# apple_all_pd1.net
KiCad netlist of a schematic drawn in EAGLE
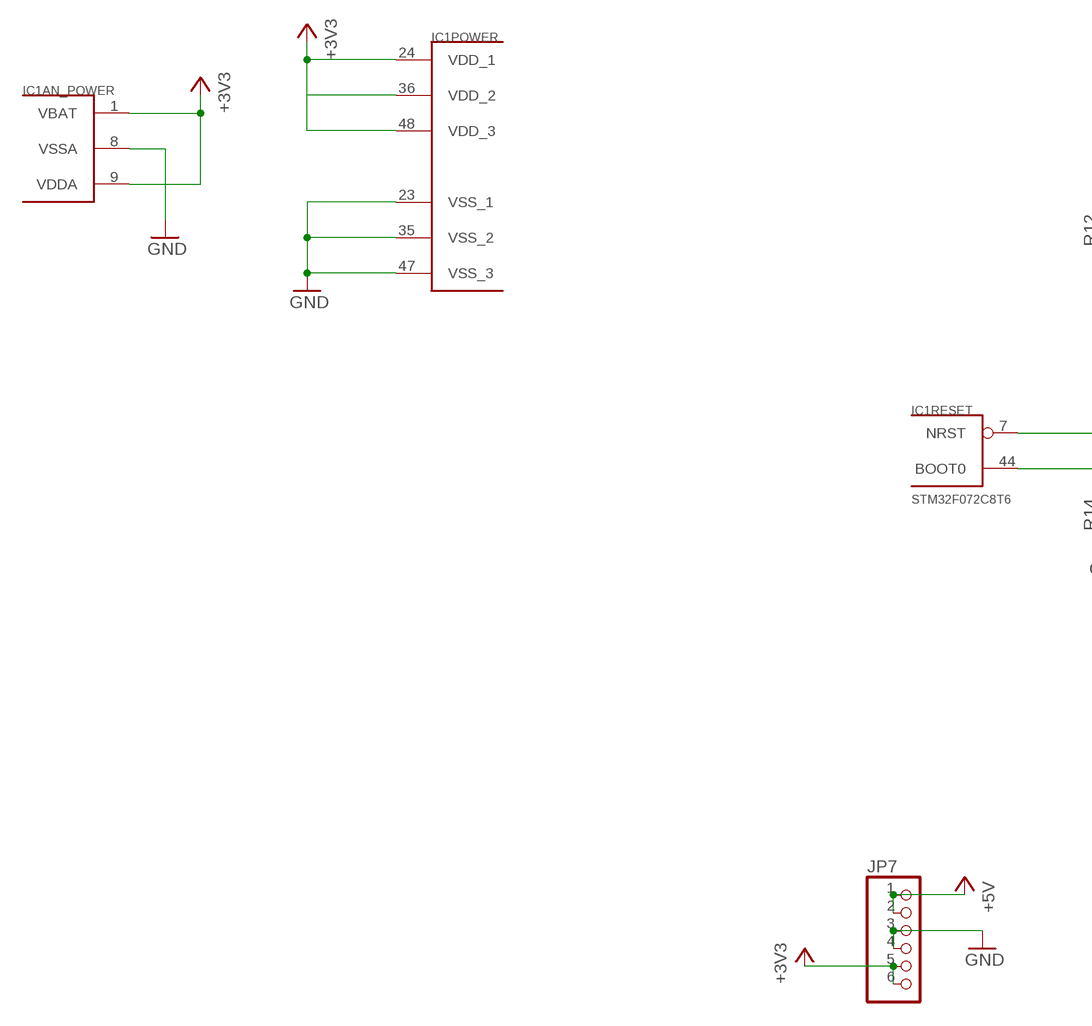
[diagram p0: schematic, sheet 1, part 1 of 2]
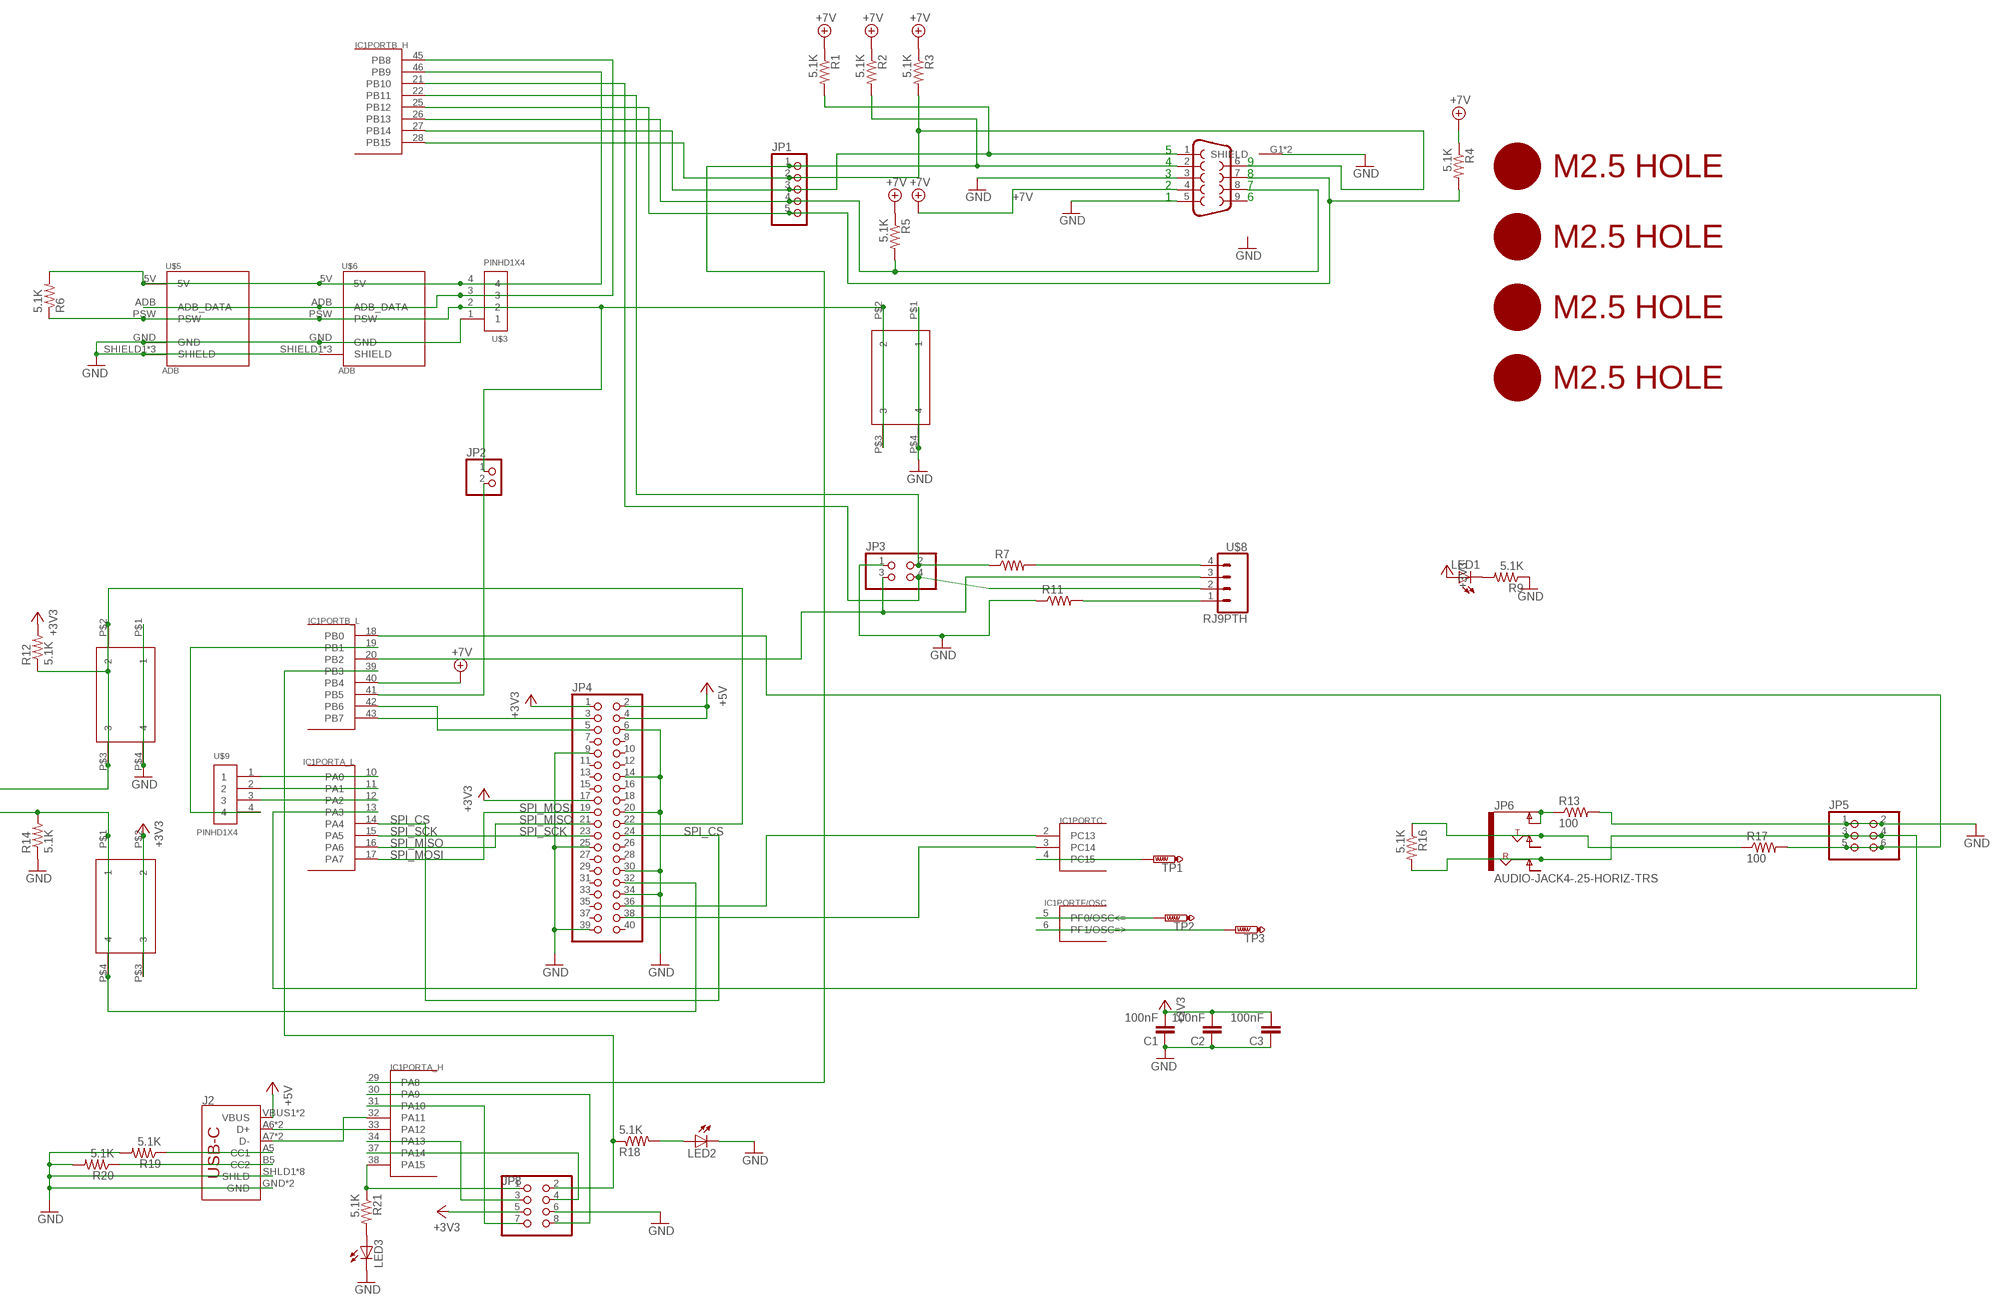
[diagram p1: schematic, sheet 1, part 2 of 2]

(export (version "E")
  (design (tool "Eeschema 10.0.6"))
  (components
    (comp (ref "C1")
      (value "100nF")
      (footprint "eagle-import:0805@1")
      (libsource (lib "eagle-import") (part "CAP0805"))
    )
    (comp (ref "C2")
      (value "100nF")
      (footprint "eagle-import:0805@1")
      (libsource (lib "eagle-import") (part "CAP0805"))
    )
    (comp (ref "C3")
      (value "100nF")
      (footprint "eagle-import:0805@1")
      (libsource (lib "eagle-import") (part "CAP0805"))
    )
    (comp (ref "IC1")
      (value "STM32F072C8T6")
      (footprint "eagle-import:TQFP48")
      (libsource (lib "eagle-import") (part "STM32F072C8T6"))
    )
    (comp (ref "J1")
      (value "DB9FEMALE")
      (footprint "eagle-import:DB9")
      (libsource (lib "eagle-import") (part "DB9FEMALE"))
    )
    (comp (ref "J2")
      (value "USB_C16PIN")
      (footprint "eagle-import:USB-C-16P")
      (libsource (lib "eagle-import") (part "USB_C16PIN"))
    )
    (comp (ref "JP1")
      (value "PINHD-1X5")
      (footprint "eagle-import:1X05")
      (libsource (lib "eagle-import") (part "PINHD-1X5"))
    )
    (comp (ref "JP2")
      (value "PINHD-1X2")
      (footprint "eagle-import:1X02")
      (libsource (lib "eagle-import") (part "PINHD-1X2"))
    )
    (comp (ref "JP3")
      (value "PINHD-2X2")
      (footprint "eagle-import:2X02")
      (libsource (lib "eagle-import") (part "PINHD-2X2"))
    )
    (comp (ref "JP4")
      (value "PINHD-2X20-BIG")
      (footprint "eagle-import:2X20-BIG")
      (libsource (lib "eagle-import") (part "PINHD-2X20-BIG"))
    )
    (comp (ref "JP5")
      (value "PINHD-2X3")
      (footprint "eagle-import:2X03")
      (libsource (lib "eagle-import") (part "PINHD-2X3"))
    )
    (comp (ref "JP6")
      (value "AUDIO-JACK4-.25-HORIZ-TRS")
      (footprint "eagle-import:AUDIO-JACK-.25-INCH-HORIZ-PTH")
      (libsource (lib "eagle-import") (part "AUDIO-JACK4-.25-HORIZ-TRS"))
    )
    (comp (ref "JP7")
      (value "PINHD-1X6CB")
      (footprint "eagle-import:1X06-CLEANBIG")
      (libsource (lib "eagle-import") (part "PINHD-1X6CB"))
    )
    (comp (ref "JP8")
      (value "PINHD-2X4")
      (footprint "eagle-import:2X04")
      (libsource (lib "eagle-import") (part "PINHD-2X4"))
    )
    (comp (ref "LED1")
      (value "LEDCHIP-LED0805")
      (footprint "eagle-import:CHIP-LED0805")
      (libsource (lib "eagle-import") (part "LEDCHIP-LED0805"))
    )
    (comp (ref "LED2")
      (value "LEDCHIP-LED0805")
      (footprint "eagle-import:CHIP-LED0805")
      (libsource (lib "eagle-import") (part "LEDCHIP-LED0805"))
    )
    (comp (ref "LED3")
      (value "LEDCHIP-LED0805")
      (footprint "eagle-import:CHIP-LED0805")
      (libsource (lib "eagle-import") (part "LEDCHIP-LED0805"))
    )
    (comp (ref "R1")
      (value "5.1K")
      (footprint "eagle-import:0805")
      (libsource (lib "eagle-import") (part "RESISTOR0805-RES"))
    )
    (comp (ref "R2")
      (value "5.1K")
      (footprint "eagle-import:0805")
      (libsource (lib "eagle-import") (part "RESISTOR0805-RES"))
    )
    (comp (ref "R3")
      (value "5.1K")
      (footprint "eagle-import:0805")
      (libsource (lib "eagle-import") (part "RESISTOR0805-RES"))
    )
    (comp (ref "R4")
      (value "5.1K")
      (footprint "eagle-import:0805")
      (libsource (lib "eagle-import") (part "RESISTOR0805-RES"))
    )
    (comp (ref "R5")
      (value "5.1K")
      (footprint "eagle-import:0805")
      (libsource (lib "eagle-import") (part "RESISTOR0805-RES"))
    )
    (comp (ref "R6")
      (value "5.1K")
      (footprint "eagle-import:0805")
      (libsource (lib "eagle-import") (part "RESISTOR0805-RES"))
    )
    (comp (ref "R7")
      (value "100")
      (footprint "eagle-import:0805")
      (libsource (lib "eagle-import") (part "RESISTOR0805-RES"))
    )
    (comp (ref "R9")
      (value "5.1K")
      (footprint "eagle-import:0805")
      (libsource (lib "eagle-import") (part "RESISTOR0805-RES"))
    )
    (comp (ref "R11")
      (value "100")
      (footprint "eagle-import:0805")
      (libsource (lib "eagle-import") (part "RESISTOR0805-RES"))
    )
    (comp (ref "R12")
      (value "5.1K")
      (footprint "eagle-import:0805")
      (libsource (lib "eagle-import") (part "RESISTOR0805-RES"))
    )
    (comp (ref "R13")
      (value "100")
      (footprint "eagle-import:0805")
      (libsource (lib "eagle-import") (part "RESISTOR0805-RES"))
    )
    (comp (ref "R14")
      (value "5.1K")
      (footprint "eagle-import:0805")
      (libsource (lib "eagle-import") (part "RESISTOR0805-RES"))
    )
    (comp (ref "R16")
      (value "5.1K")
      (footprint "eagle-import:0805")
      (libsource (lib "eagle-import") (part "RESISTOR0805-RES"))
    )
    (comp (ref "R17")
      (value "100")
      (footprint "eagle-import:0805")
      (libsource (lib "eagle-import") (part "RESISTOR0805-RES"))
    )
    (comp (ref "R18")
      (value "5.1K")
      (footprint "eagle-import:0805")
      (libsource (lib "eagle-import") (part "RESISTOR0805-RES"))
    )
    (comp (ref "R19")
      (value "5.1K")
      (footprint "eagle-import:0805")
      (libsource (lib "eagle-import") (part "RESISTOR0805-RES"))
    )
    (comp (ref "R20")
      (value "5.1K")
      (footprint "eagle-import:0805")
      (libsource (lib "eagle-import") (part "RESISTOR0805-RES"))
    )
    (comp (ref "R21")
      (value "5.1K")
      (footprint "eagle-import:0805")
      (libsource (lib "eagle-import") (part "RESISTOR0805-RES"))
    )
    (comp (ref "SW1")
      (value "324_SW")
      (footprint "eagle-import:342_SWICH_FOOT")
      (libsource (lib "eagle-import") (part "324_SW"))
    )
    (comp (ref "SW2")
      (value "324_SW")
      (footprint "eagle-import:342_SWICH_FOOT")
      (libsource (lib "eagle-import") (part "324_SW"))
    )
    (comp (ref "SW3")
      (value "324_SW")
      (footprint "eagle-import:342_SWICH_FOOT")
      (libsource (lib "eagle-import") (part "324_SW"))
    )
    (comp (ref "TP1")
      (value "PTR1TP14R")
      (footprint "eagle-import:TP14R")
      (libsource (lib "eagle-import") (part "PTR1TP14R"))
    )
    (comp (ref "TP2")
      (value "PTR1TP14R")
      (footprint "eagle-import:TP14R")
      (libsource (lib "eagle-import") (part "PTR1TP14R"))
    )
    (comp (ref "TP3")
      (value "PTR1TP14R")
      (footprint "eagle-import:TP14R")
      (libsource (lib "eagle-import") (part "PTR1TP14R"))
    )
    (comp (ref "U$1")
      (value "M2.5HOLE")
      (footprint "eagle-import:M2.5HOLE")
      (libsource (lib "eagle-import") (part "M2.5HOLE"))
    )
    (comp (ref "U$2")
      (value "M2.5HOLE")
      (footprint "eagle-import:M2.5HOLE")
      (libsource (lib "eagle-import") (part "M2.5HOLE"))
    )
    (comp (ref "U$3")
      (value "PINHD1X4")
      (footprint "eagle-import:1X04-CLEANBIG")
      (libsource (lib "eagle-import") (part "PINHD1X4"))
    )
    (comp (ref "U$4")
      (value "M2.5HOLE")
      (footprint "eagle-import:M2.5HOLE")
      (libsource (lib "eagle-import") (part "M2.5HOLE"))
    )
    (comp (ref "U$5")
      (value "ADB")
      (footprint "eagle-import:DIN4")
      (libsource (lib "eagle-import") (part "ADB"))
    )
    (comp (ref "U$6")
      (value "ADB")
      (footprint "eagle-import:DIN4")
      (libsource (lib "eagle-import") (part "ADB"))
    )
    (comp (ref "U$7")
      (value "M2.5HOLE")
      (footprint "eagle-import:M2.5HOLE")
      (libsource (lib "eagle-import") (part "M2.5HOLE"))
    )
    (comp (ref "U$8")
      (value "RJ9PTH")
      (footprint "eagle-import:RJ9")
      (libsource (lib "eagle-import") (part "RJ9PTH"))
    )
    (comp (ref "U$9")
      (value "PINHD1X4")
      (footprint "eagle-import:1X04-CLEANBIG")
      (libsource (lib "eagle-import") (part "PINHD1X4"))
    )
  )
  (nets
    (net (code "1") (name "+3V3") (class "Default")
      (node (ref "C1") (pin "2") (pinfunction "2_2") (pintype "passive"))
      (node (ref "C2") (pin "2") (pinfunction "2_2") (pintype "passive"))
      (node (ref "C3") (pin "2") (pinfunction "2_2") (pintype "passive"))
      (node (ref "IC1") (pin "1") (pinfunction "VBAT_1") (pintype "power_in"))
      (node (ref "IC1") (pin "24") (pinfunction "VDD_1_24") (pintype "power_in"))
      (node (ref "IC1") (pin "36") (pinfunction "VDD_2_36") (pintype "power_in"))
      (node (ref "IC1") (pin "48") (pinfunction "VDD_3_48") (pintype "power_in"))
      (node (ref "IC1") (pin "9") (pinfunction "VDDA_9") (pintype "power_in"))
      (node (ref "JP4") (pin "1") (pinfunction "1_1") (pintype "passive"))
      (node (ref "JP4") (pin "17") (pinfunction "17_17") (pintype "passive"))
      (node (ref "JP7") (pin "5") (pinfunction "5_5") (pintype "passive"))
      (node (ref "JP7") (pin "6") (pinfunction "6_6") (pintype "passive"))
      (node (ref "JP8") (pin "5") (pinfunction "5_5") (pintype "passive"))
      (node (ref "LED1") (pin "A") (pinfunction "A_A") (pintype "passive"))
      (node (ref "R12") (pin "2") (pinfunction "2_2") (pintype "passive"))
      (node (ref "SW3") (pin "P$2") (pinfunction "2_P$2") (pintype "bidirectional"))
      (node (ref "SW3") (pin "P$3") (pinfunction "3_P$3") (pintype "bidirectional"))
    )
    (net (code "2") (name "+5V") (class "Default")
      (node (ref "J2") (pin "VBUS1") (pinfunction "VBUS_VBUS1") (pintype "bidirectional"))
      (node (ref "J2") (pin "VBUS2") (pinfunction "VBUS_VBUS2") (pintype "bidirectional"))
      (node (ref "JP4") (pin "2") (pinfunction "2_2") (pintype "passive"))
      (node (ref "JP4") (pin "4") (pinfunction "4_4") (pintype "passive"))
      (node (ref "JP7") (pin "1") (pinfunction "1_1") (pintype "passive"))
      (node (ref "JP7") (pin "2") (pinfunction "2_2") (pintype "passive"))
    )
    (net (code "3") (name "+7V") (class "Default")
      (node (ref "IC1") (pin "40") (pinfunction "PB4_40") (pintype "bidirectional"))
      (node (ref "J1") (pin "4") (pinfunction "4_4") (pintype "passive"))
      (node (ref "R1") (pin "1") (pinfunction "1_1") (pintype "passive"))
      (node (ref "R2") (pin "1") (pinfunction "1_1") (pintype "passive"))
      (node (ref "R3") (pin "1") (pinfunction "1_1") (pintype "passive"))
      (node (ref "R4") (pin "1") (pinfunction "1_1") (pintype "passive"))
      (node (ref "R5") (pin "1") (pinfunction "1_1") (pintype "passive"))
    )
    (net (code "4") (name "/SPI_CS") (class "Default")
      (node (ref "IC1") (pin "14") (pinfunction "PA4_14") (pintype "bidirectional"))
      (node (ref "JP4") (pin "24") (pinfunction "24_24") (pintype "passive"))
    )
    (net (code "5") (name "/SPI_MISO") (class "Default")
      (node (ref "IC1") (pin "16") (pinfunction "PA6_16") (pintype "bidirectional"))
      (node (ref "JP4") (pin "21") (pinfunction "21_21") (pintype "passive"))
    )
    (net (code "6") (name "/SPI_MOSI") (class "Default")
      (node (ref "IC1") (pin "17") (pinfunction "PA7_17") (pintype "bidirectional"))
      (node (ref "JP4") (pin "19") (pinfunction "19_19") (pintype "passive"))
    )
    (net (code "7") (name "/SPI_SCK") (class "Default")
      (node (ref "IC1") (pin "15") (pinfunction "PA5_15") (pintype "bidirectional"))
      (node (ref "JP4") (pin "23") (pinfunction "23_23") (pintype "passive"))
    )
    (net (code "8") (name "GND") (class "Default")
      (node (ref "C1") (pin "1") (pinfunction "1_1") (pintype "passive"))
      (node (ref "C2") (pin "1") (pinfunction "1_1") (pintype "passive"))
      (node (ref "C3") (pin "1") (pinfunction "1_1") (pintype "passive"))
      (node (ref "IC1") (pin "23") (pinfunction "VSS_1_23") (pintype "power_in"))
      (node (ref "IC1") (pin "35") (pinfunction "VSS_2_35") (pintype "power_in"))
      (node (ref "IC1") (pin "47") (pinfunction "VSS_3_47") (pintype "power_in"))
      (node (ref "IC1") (pin "8") (pinfunction "VSSA_8") (pintype "power_in"))
      (node (ref "J1") (pin "3") (pinfunction "3_3") (pintype "passive"))
      (node (ref "J1") (pin "5") (pinfunction "5_5") (pintype "passive"))
      (node (ref "J1") (pin "G1") (pinfunction "SHIELD_G1") (pintype "bidirectional"))
      (node (ref "J1") (pin "G2") (pinfunction "SHIELD_G2") (pintype "bidirectional"))
      (node (ref "J2") (pin "GND") (pinfunction "GND_GND") (pintype "bidirectional"))
      (node (ref "J2") (pin "GND2") (pinfunction "GND_GND2") (pintype "bidirectional"))
      (node (ref "J2") (pin "SHLD1") (pinfunction "SHLD_SHLD1") (pintype "bidirectional"))
      (node (ref "J2") (pin "SHLD2") (pinfunction "SHLD_SHLD2") (pintype "bidirectional"))
      (node (ref "J2") (pin "SHLD3") (pinfunction "SHLD_SHLD3") (pintype "bidirectional"))
      (node (ref "J2") (pin "SHLD4") (pinfunction "SHLD_SHLD4") (pintype "bidirectional"))
      (node (ref "J2") (pin "SHLD5") (pinfunction "SHLD_SHLD5") (pintype "bidirectional"))
      (node (ref "J2") (pin "SHLD6") (pinfunction "SHLD_SHLD6") (pintype "bidirectional"))
      (node (ref "J2") (pin "SHLD7") (pinfunction "SHLD_SHLD7") (pintype "bidirectional"))
      (node (ref "J2") (pin "SHLD8") (pinfunction "SHLD_SHLD8") (pintype "bidirectional"))
      (node (ref "JP3") (pin "1") (pinfunction "1_1") (pintype "passive"))
      (node (ref "JP4") (pin "14") (pinfunction "14_14") (pintype "passive"))
      (node (ref "JP4") (pin "20") (pinfunction "20_20") (pintype "passive"))
      (node (ref "JP4") (pin "25") (pinfunction "25_25") (pintype "passive"))
      (node (ref "JP4") (pin "30") (pinfunction "30_30") (pintype "passive"))
      (node (ref "JP4") (pin "34") (pinfunction "34_34") (pintype "passive"))
      (node (ref "JP4") (pin "39") (pinfunction "39_39") (pintype "passive"))
      (node (ref "JP4") (pin "6") (pinfunction "6_6") (pintype "passive"))
      (node (ref "JP4") (pin "9") (pinfunction "9_9") (pintype "passive"))
      (node (ref "JP5") (pin "1") (pinfunction "1_1") (pintype "passive"))
      (node (ref "JP5") (pin "2") (pinfunction "2_2") (pintype "passive"))
      (node (ref "JP7") (pin "3") (pinfunction "3_3") (pintype "passive"))
      (node (ref "JP7") (pin "4") (pinfunction "4_4") (pintype "passive"))
      (node (ref "JP8") (pin "6") (pinfunction "6_6") (pintype "passive"))
      (node (ref "LED2") (pin "C") (pinfunction "C_C") (pintype "passive"))
      (node (ref "LED3") (pin "C") (pinfunction "C_C") (pintype "passive"))
      (node (ref "R11") (pin "1") (pinfunction "1_1") (pintype "passive"))
      (node (ref "R13") (pin "2") (pinfunction "2_2") (pintype "passive"))
      (node (ref "R14") (pin "1") (pinfunction "1_1") (pintype "passive"))
      (node (ref "R19") (pin "2") (pinfunction "2_2") (pintype "passive"))
      (node (ref "R20") (pin "2") (pinfunction "2_2") (pintype "passive"))
      (node (ref "R9") (pin "1") (pinfunction "1_1") (pintype "passive"))
      (node (ref "SW1") (pin "P$1") (pinfunction "1_P$1") (pintype "bidirectional"))
      (node (ref "SW1") (pin "P$4") (pinfunction "4_P$4") (pintype "bidirectional"))
      (node (ref "SW2") (pin "P$1") (pinfunction "1_P$1") (pintype "bidirectional"))
      (node (ref "SW2") (pin "P$4") (pinfunction "4_P$4") (pintype "bidirectional"))
      (node (ref "U$3") (pin "1") (pinfunction "1_1") (pintype "bidirectional"))
      (node (ref "U$5") (pin "GND") (pinfunction "GND_GND") (pintype "bidirectional"))
      (node (ref "U$5") (pin "SHIELD1") (pinfunction "SHIELD_SHIELD1") (pintype "bidirectional"))
      (node (ref "U$5") (pin "SHIELD2") (pinfunction "SHIELD_SHIELD2") (pintype "bidirectional"))
      (node (ref "U$5") (pin "SHIELD3") (pinfunction "SHIELD_SHIELD3") (pintype "bidirectional"))
      (node (ref "U$6") (pin "GND") (pinfunction "GND_GND") (pintype "bidirectional"))
      (node (ref "U$6") (pin "SHIELD1") (pinfunction "SHIELD_SHIELD1") (pintype "bidirectional"))
      (node (ref "U$6") (pin "SHIELD2") (pinfunction "SHIELD_SHIELD2") (pintype "bidirectional"))
      (node (ref "U$6") (pin "SHIELD3") (pinfunction "SHIELD_SHIELD3") (pintype "bidirectional"))
    )
    (net (code "9") (name "Net-(IC1B-PA8)") (class "Default")
      (node (ref "IC1") (pin "29") (pinfunction "PA8_29") (pintype "bidirectional"))
      (node (ref "J1") (pin "2") (pinfunction "2_2") (pintype "passive"))
      (node (ref "JP1") (pin "1") (pinfunction "1_1") (pintype "passive"))
      (node (ref "R2") (pin "2") (pinfunction "2_2") (pintype "passive"))
    )
    (net (code "10") (name "Net-(IC1B-PA9)") (class "Default")
      (node (ref "IC1") (pin "30") (pinfunction "PA9_30") (pintype "bidirectional"))
      (node (ref "JP8") (pin "8") (pinfunction "8_8") (pintype "passive"))
    )
    (net (code "11") (name "Net-(IC1B-PA10)") (class "Default")
      (node (ref "IC1") (pin "31") (pinfunction "PA10_31") (pintype "bidirectional"))
      (node (ref "JP8") (pin "7") (pinfunction "7_7") (pintype "passive"))
    )
    (net (code "12") (name "Net-(IC1B-PA11)") (class "Default")
      (node (ref "IC1") (pin "32") (pinfunction "PA11_32") (pintype "bidirectional"))
      (node (ref "J2") (pin "A7") (pinfunction "D-_A7") (pintype "bidirectional"))
      (node (ref "J2") (pin "B7") (pinfunction "D-_B7") (pintype "bidirectional"))
    )
    (net (code "13") (name "Net-(IC1B-PA12)") (class "Default")
      (node (ref "IC1") (pin "33") (pinfunction "PA12_33") (pintype "bidirectional"))
      (node (ref "J2") (pin "A6") (pinfunction "D+_A6") (pintype "bidirectional"))
      (node (ref "J2") (pin "B6") (pinfunction "D+_B6") (pintype "bidirectional"))
    )
    (net (code "14") (name "Net-(IC1B-PA13)") (class "Default")
      (node (ref "IC1") (pin "34") (pinfunction "PA13_34") (pintype "bidirectional"))
      (node (ref "JP8") (pin "3") (pinfunction "3_3") (pintype "passive"))
    )
    (net (code "15") (name "Net-(IC1B-PA14)") (class "Default")
      (node (ref "IC1") (pin "37") (pinfunction "PA14_37") (pintype "bidirectional"))
      (node (ref "JP8") (pin "4") (pinfunction "4_4") (pintype "passive"))
    )
    (net (code "16") (name "Net-(IC1B-PA15)") (class "Default")
      (node (ref "IC1") (pin "38") (pinfunction "PA15_38") (pintype "bidirectional"))
      (node (ref "JP8") (pin "1") (pinfunction "1_1") (pintype "passive"))
      (node (ref "R21") (pin "1") (pinfunction "1_1") (pintype "passive"))
    )
    (net (code "17") (name "Net-(IC1C-PA0)") (class "Default")
      (node (ref "IC1") (pin "10") (pinfunction "PA0_10") (pintype "bidirectional"))
      (node (ref "U$9") (pin "1") (pinfunction "1_1") (pintype "bidirectional"))
    )
    (net (code "18") (name "Net-(IC1C-PA1)") (class "Default")
      (node (ref "IC1") (pin "11") (pinfunction "PA1_11") (pintype "bidirectional"))
      (node (ref "U$9") (pin "2") (pinfunction "2_2") (pintype "bidirectional"))
    )
    (net (code "19") (name "Net-(IC1C-PA2)") (class "Default")
      (node (ref "IC1") (pin "12") (pinfunction "PA2_12") (pintype "bidirectional"))
      (node (ref "U$9") (pin "3") (pinfunction "3_3") (pintype "bidirectional"))
    )
    (net (code "20") (name "Net-(IC1C-PA3)") (class "Default")
      (node (ref "IC1") (pin "13") (pinfunction "PA3_13") (pintype "bidirectional"))
      (node (ref "JP5") (pin "3") (pinfunction "3_3") (pintype "passive"))
      (node (ref "JP5") (pin "4") (pinfunction "4_4") (pintype "passive"))
      (node (ref "JP6") (pin "RING") (pinfunction "RING_RING") (pintype "bidirectional"))
      (node (ref "R16") (pin "2") (pinfunction "2_2") (pintype "passive"))
    )
    (net (code "21") (name "Net-(IC1D-PB8)") (class "Default")
      (node (ref "IC1") (pin "45") (pinfunction "PB8_45") (pintype "bidirectional"))
      (node (ref "U$3") (pin "3") (pinfunction "3_3") (pintype "bidirectional"))
      (node (ref "U$5") (pin "ADB") (pinfunction "ADB_DATA_ADB") (pintype "bidirectional"))
      (node (ref "U$6") (pin "ADB") (pinfunction "ADB_DATA_ADB") (pintype "bidirectional"))
    )
    (net (code "22") (name "Net-(IC1D-PB9)") (class "Default")
      (node (ref "IC1") (pin "46") (pinfunction "PB9_46") (pintype "bidirectional"))
      (node (ref "R6") (pin "2") (pinfunction "2_2") (pintype "passive"))
      (node (ref "U$3") (pin "4") (pinfunction "4_4") (pintype "bidirectional"))
      (node (ref "U$5") (pin "5V") (pinfunction "5V_5V") (pintype "bidirectional"))
      (node (ref "U$6") (pin "5V") (pinfunction "5V_5V") (pintype "bidirectional"))
    )
    (net (code "23") (name "Net-(IC1D-PB10)") (class "Default")
      (node (ref "IC1") (pin "21") (pinfunction "PB10_21") (pintype "bidirectional"))
      (node (ref "JP3") (pin "4") (pinfunction "4_4") (pintype "passive"))
      (node (ref "U$8") (pin "2") (pinfunction "2_2") (pintype "passive"))
    )
    (net (code "24") (name "Net-(IC1D-PB11)") (class "Default")
      (node (ref "IC1") (pin "22") (pinfunction "PB11_22") (pintype "bidirectional"))
      (node (ref "JP3") (pin "2") (pinfunction "2_2") (pintype "passive"))
      (node (ref "R7") (pin "1") (pinfunction "1_1") (pintype "passive"))
    )
    (net (code "25") (name "Net-(IC1D-PB12)") (class "Default")
      (node (ref "IC1") (pin "25") (pinfunction "PB12_25") (pintype "bidirectional"))
      (node (ref "J1") (pin "7") (pinfunction "7_7") (pintype "passive"))
      (node (ref "JP1") (pin "5") (pinfunction "5_5") (pintype "passive"))
      (node (ref "R4") (pin "2") (pinfunction "2_2") (pintype "passive"))
    )
    (net (code "26") (name "Net-(IC1D-PB13)") (class "Default")
      (node (ref "IC1") (pin "26") (pinfunction "PB13_26") (pintype "bidirectional"))
      (node (ref "J1") (pin "8") (pinfunction "8_8") (pintype "passive"))
      (node (ref "JP1") (pin "4") (pinfunction "4_4") (pintype "passive"))
      (node (ref "R5") (pin "2") (pinfunction "2_2") (pintype "passive"))
    )
    (net (code "27") (name "Net-(IC1D-PB14)") (class "Default")
      (node (ref "IC1") (pin "27") (pinfunction "PB14_27") (pintype "bidirectional"))
      (node (ref "J1") (pin "1") (pinfunction "1_1") (pintype "passive"))
      (node (ref "JP1") (pin "3") (pinfunction "3_3") (pintype "passive"))
      (node (ref "R1") (pin "2") (pinfunction "2_2") (pintype "passive"))
    )
    (net (code "28") (name "Net-(IC1D-PB15)") (class "Default")
      (node (ref "IC1") (pin "28") (pinfunction "PB15_28") (pintype "bidirectional"))
      (node (ref "J1") (pin "6") (pinfunction "6_6") (pintype "passive"))
      (node (ref "JP1") (pin "2") (pinfunction "2_2") (pintype "passive"))
      (node (ref "R3") (pin "2") (pinfunction "2_2") (pintype "passive"))
    )
    (net (code "29") (name "Net-(IC1E-PB0)") (class "Default")
      (node (ref "IC1") (pin "18") (pinfunction "PB0_18") (pintype "bidirectional"))
      (node (ref "JP5") (pin "5") (pinfunction "5_5") (pintype "passive"))
      (node (ref "JP5") (pin "6") (pinfunction "6_6") (pintype "passive"))
      (node (ref "R17") (pin "2") (pinfunction "2_2") (pintype "passive"))
    )
    (net (code "30") (name "Net-(IC1E-PB1)") (class "Default")
      (node (ref "IC1") (pin "19") (pinfunction "PB1_19") (pintype "bidirectional"))
      (node (ref "U$9") (pin "4") (pinfunction "4_4") (pintype "bidirectional"))
    )
    (net (code "31") (name "Net-(IC1E-PB2)") (class "Default")
      (node (ref "IC1") (pin "20") (pinfunction "PB2_20") (pintype "bidirectional"))
      (node (ref "JP3") (pin "3") (pinfunction "3_3") (pintype "passive"))
      (node (ref "U$8") (pin "3") (pinfunction "3_3") (pintype "passive"))
    )
    (net (code "32") (name "Net-(IC1E-PB3)") (class "Default")
      (node (ref "IC1") (pin "39") (pinfunction "PB3_39") (pintype "bidirectional"))
      (node (ref "JP8") (pin "2") (pinfunction "2_2") (pintype "passive"))
      (node (ref "R18") (pin "1") (pinfunction "1_1") (pintype "passive"))
    )
    (net (code "33") (name "Net-(IC1E-PB5)") (class "Default")
      (node (ref "IC1") (pin "41") (pinfunction "PB5_41") (pintype "bidirectional"))
      (node (ref "JP2") (pin "2") (pinfunction "2_2") (pintype "passive"))
    )
    (net (code "34") (name "Net-(IC1E-PB6)") (class "Default")
      (node (ref "IC1") (pin "42") (pinfunction "PB6_42") (pintype "bidirectional"))
      (node (ref "JP4") (pin "5") (pinfunction "5_5") (pintype "passive"))
    )
    (net (code "35") (name "Net-(IC1E-PB7)") (class "Default")
      (node (ref "IC1") (pin "43") (pinfunction "PB7_43") (pintype "bidirectional"))
      (node (ref "JP4") (pin "3") (pinfunction "3_3") (pintype "passive"))
    )
    (net (code "36") (name "Net-(IC1F-PC13)") (class "Default")
      (node (ref "IC1") (pin "2") (pinfunction "PC13_2") (pintype "bidirectional"))
      (node (ref "JP4") (pin "36") (pinfunction "36_36") (pintype "passive"))
    )
    (net (code "37") (name "Net-(IC1F-PC14)") (class "Default")
      (node (ref "IC1") (pin "3") (pinfunction "PC14_3") (pintype "bidirectional"))
      (node (ref "JP4") (pin "38") (pinfunction "38_38") (pintype "passive"))
    )
    (net (code "38") (name "Net-(IC1F-PC15)") (class "Default")
      (node (ref "IC1") (pin "4") (pinfunction "PC15_4") (pintype "bidirectional"))
      (node (ref "TP1") (pin "TP") (pinfunction "TP_TP") (pintype "input"))
    )
    (net (code "39") (name "Net-(IC1G-PF0{slash}OSC<=)") (class "Default")
      (node (ref "IC1") (pin "5") (pinfunction "PF0/OSC<=_5") (pintype "bidirectional"))
      (node (ref "TP2") (pin "TP") (pinfunction "TP_TP") (pintype "input"))
    )
    (net (code "40") (name "Net-(IC1G-PF1{slash}OSC=>)") (class "Default")
      (node (ref "IC1") (pin "6") (pinfunction "PF1/OSC=>_6") (pintype "bidirectional"))
      (node (ref "TP3") (pin "TP") (pinfunction "TP_TP") (pintype "input"))
    )
    (net (code "41") (name "Net-(IC1I-BOOT0)") (class "Default")
      (node (ref "IC1") (pin "44") (pinfunction "BOOT0_44") (pintype "input"))
      (node (ref "JP4") (pin "32") (pinfunction "32_32") (pintype "passive"))
      (node (ref "R14") (pin "2") (pinfunction "2_2") (pintype "passive"))
      (node (ref "SW3") (pin "P$1") (pinfunction "1_P$1") (pintype "bidirectional"))
      (node (ref "SW3") (pin "P$4") (pinfunction "4_P$4") (pintype "bidirectional"))
    )
    (net (code "42") (name "Net-(IC1I-NRST)") (class "Default")
      (node (ref "IC1") (pin "7") (pinfunction "NRST_7") (pintype "input"))
      (node (ref "JP4") (pin "22") (pinfunction "22_22") (pintype "passive"))
      (node (ref "R12") (pin "1") (pinfunction "1_1") (pintype "passive"))
      (node (ref "SW2") (pin "P$2") (pinfunction "2_P$2") (pintype "bidirectional"))
      (node (ref "SW2") (pin "P$3") (pinfunction "3_P$3") (pintype "bidirectional"))
    )
    (net (code "43") (name "Net-(J2-CC1)") (class "Default")
      (node (ref "J2") (pin "A5") (pinfunction "CC1_A5") (pintype "bidirectional"))
      (node (ref "R19") (pin "1") (pinfunction "1_1") (pintype "passive"))
    )
    (net (code "44") (name "Net-(J2-CC2)") (class "Default")
      (node (ref "J2") (pin "B5") (pinfunction "CC2_B5") (pintype "bidirectional"))
      (node (ref "R20") (pin "1") (pinfunction "1_1") (pintype "passive"))
    )
    (net (code "45") (name "Net-(JP6-EARTH)") (class "Default")
      (node (ref "JP6") (pin "SLEEVE") (pinfunction "EARTH_SLEEVE") (pintype "bidirectional"))
      (node (ref "JP6") (pin "SLEEVE-NORM") (pinfunction "EARTH-NORM_SLEEVE-NORM") (pintype "bidirectional"))
      (node (ref "R13") (pin "1") (pinfunction "1_1") (pintype "passive"))
    )
    (net (code "46") (name "Net-(JP6-PadTIP)") (class "Default")
      (node (ref "JP6") (pin "TIP") (pinfunction "TIP_TIP") (pintype "bidirectional"))
      (node (ref "R16") (pin "1") (pinfunction "1_1") (pintype "passive"))
      (node (ref "R17") (pin "1") (pinfunction "1_1") (pintype "passive"))
    )
    (net (code "47") (name "Net-(LED1-PadC)") (class "Default")
      (node (ref "LED1") (pin "C") (pinfunction "C_C") (pintype "passive"))
      (node (ref "R9") (pin "2") (pinfunction "2_2") (pintype "passive"))
    )
    (net (code "48") (name "Net-(LED2-PadA)") (class "Default")
      (node (ref "LED2") (pin "A") (pinfunction "A_A") (pintype "passive"))
      (node (ref "R18") (pin "2") (pinfunction "2_2") (pintype "passive"))
    )
    (net (code "49") (name "Net-(LED3-PadA)") (class "Default")
      (node (ref "LED3") (pin "A") (pinfunction "A_A") (pintype "passive"))
      (node (ref "R21") (pin "2") (pinfunction "2_2") (pintype "passive"))
    )
    (net (code "50") (name "Net-(R7-Pad2)") (class "Default")
      (node (ref "R7") (pin "2") (pinfunction "2_2") (pintype "passive"))
      (node (ref "U$8") (pin "4") (pinfunction "4_4") (pintype "passive"))
    )
    (net (code "51") (name "Net-(R11-Pad2)") (class "Default")
      (node (ref "R11") (pin "2") (pinfunction "2_2") (pintype "passive"))
      (node (ref "U$8") (pin "1") (pinfunction "1_1") (pintype "passive"))
    )
    (net (code "52") (name "Net-(SW1-2)") (class "Default")
      (node (ref "JP2") (pin "1") (pinfunction "1_1") (pintype "passive"))
      (node (ref "R6") (pin "1") (pinfunction "1_1") (pintype "passive"))
      (node (ref "SW1") (pin "P$2") (pinfunction "2_P$2") (pintype "bidirectional"))
      (node (ref "SW1") (pin "P$3") (pinfunction "3_P$3") (pintype "bidirectional"))
      (node (ref "U$3") (pin "2") (pinfunction "2_2") (pintype "bidirectional"))
      (node (ref "U$5") (pin "PSW") (pinfunction "PSW_PSW") (pintype "bidirectional"))
      (node (ref "U$6") (pin "PSW") (pinfunction "PSW_PSW") (pintype "bidirectional"))
    )
    (net (code "53") (name "unconnected-(J1-Pad9)") (class "Default")
      (node (ref "J1") (pin "9") (pinfunction "9_9") (pintype "passive"))
    )
    (net (code "54") (name "unconnected-(JP4-Pad7)") (class "Default")
      (node (ref "JP4") (pin "7") (pinfunction "7_7") (pintype "passive"))
    )
    (net (code "55") (name "unconnected-(JP4-Pad8)") (class "Default")
      (node (ref "JP4") (pin "8") (pinfunction "8_8") (pintype "passive"))
    )
    (net (code "56") (name "unconnected-(JP4-Pad10)") (class "Default")
      (node (ref "JP4") (pin "10") (pinfunction "10_10") (pintype "passive"))
    )
    (net (code "57") (name "unconnected-(JP4-Pad11)") (class "Default")
      (node (ref "JP4") (pin "11") (pinfunction "11_11") (pintype "passive"))
    )
    (net (code "58") (name "unconnected-(JP4-Pad12)") (class "Default")
      (node (ref "JP4") (pin "12") (pinfunction "12_12") (pintype "passive"))
    )
    (net (code "59") (name "unconnected-(JP4-Pad13)") (class "Default")
      (node (ref "JP4") (pin "13") (pinfunction "13_13") (pintype "passive"))
    )
    (net (code "60") (name "unconnected-(JP4-Pad15)") (class "Default")
      (node (ref "JP4") (pin "15") (pinfunction "15_15") (pintype "passive"))
    )
    (net (code "61") (name "unconnected-(JP4-Pad16)") (class "Default")
      (node (ref "JP4") (pin "16") (pinfunction "16_16") (pintype "passive"))
    )
    (net (code "62") (name "unconnected-(JP4-Pad18)") (class "Default")
      (node (ref "JP4") (pin "18") (pinfunction "18_18") (pintype "passive"))
    )
    (net (code "63") (name "unconnected-(JP4-Pad26)") (class "Default")
      (node (ref "JP4") (pin "26") (pinfunction "26_26") (pintype "passive"))
    )
    (net (code "64") (name "unconnected-(JP4-Pad27)") (class "Default")
      (node (ref "JP4") (pin "27") (pinfunction "27_27") (pintype "passive"))
    )
    (net (code "65") (name "unconnected-(JP4-Pad28)") (class "Default")
      (node (ref "JP4") (pin "28") (pinfunction "28_28") (pintype "passive"))
    )
    (net (code "66") (name "unconnected-(JP4-Pad29)") (class "Default")
      (node (ref "JP4") (pin "29") (pinfunction "29_29") (pintype "passive"))
    )
    (net (code "67") (name "unconnected-(JP4-Pad31)") (class "Default")
      (node (ref "JP4") (pin "31") (pinfunction "31_31") (pintype "passive"))
    )
    (net (code "68") (name "unconnected-(JP4-Pad33)") (class "Default")
      (node (ref "JP4") (pin "33") (pinfunction "33_33") (pintype "passive"))
    )
    (net (code "69") (name "unconnected-(JP4-Pad35)") (class "Default")
      (node (ref "JP4") (pin "35") (pinfunction "35_35") (pintype "passive"))
    )
    (net (code "70") (name "unconnected-(JP4-Pad37)") (class "Default")
      (node (ref "JP4") (pin "37") (pinfunction "37_37") (pintype "passive"))
    )
    (net (code "71") (name "unconnected-(JP4-Pad40)") (class "Default")
      (node (ref "JP4") (pin "40") (pinfunction "40_40") (pintype "passive"))
    )
    (net (code "72") (name "unconnected-(JP6-PadRING-NORM)") (class "Default")
      (node (ref "JP6") (pin "RING-NORM") (pinfunction "RING-NORM_RING-NORM") (pintype "bidirectional"))
    )
    (net (code "73") (name "unconnected-(JP6-PadTIP-NORM)") (class "Default")
      (node (ref "JP6") (pin "TIP-NORM") (pinfunction "TIP-NORM_TIP-NORM") (pintype "bidirectional"))
    )
  )
)
